# 13-AX88179A.net
KiCad netlist of a schematic drawn in Altium Designer
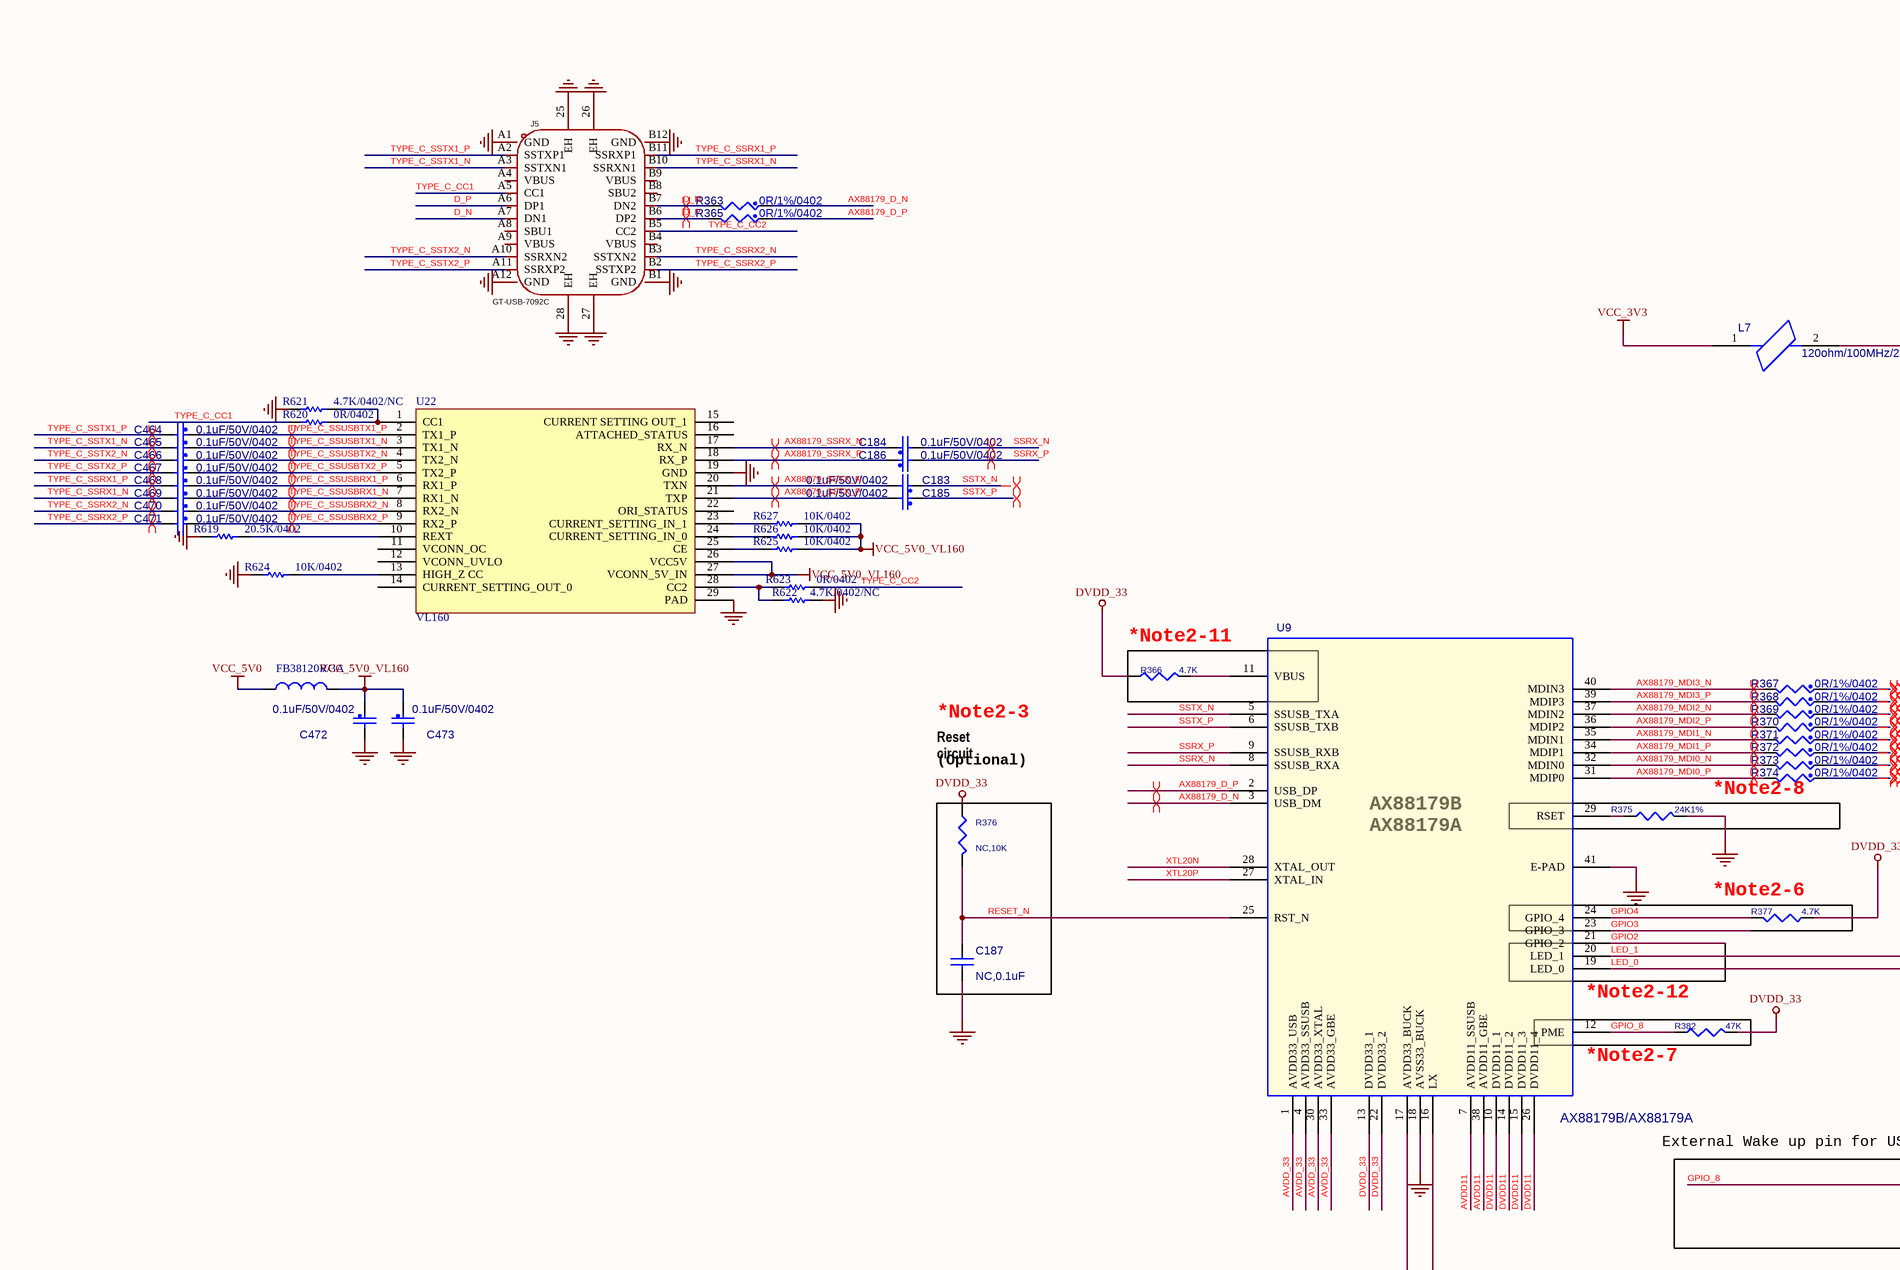
[diagram p0: 13-AX88179A.SchDoc, top left]
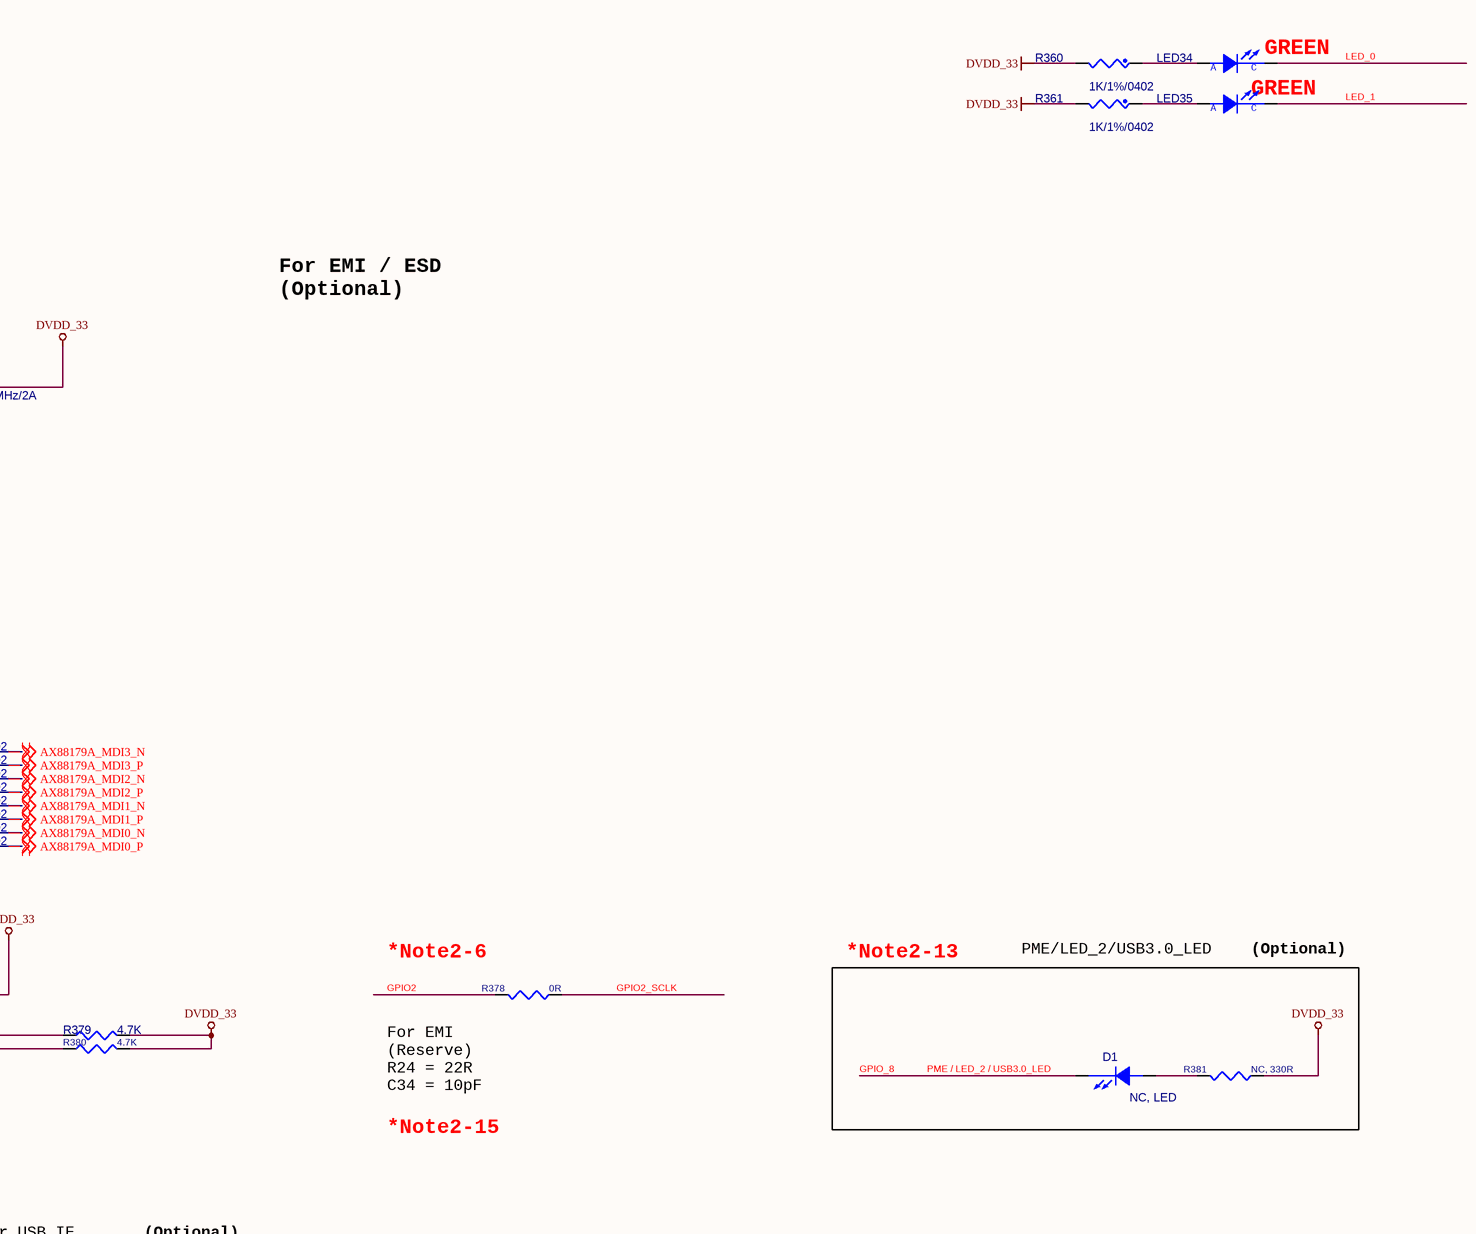
[diagram p1: 13-AX88179A.SchDoc, top right]
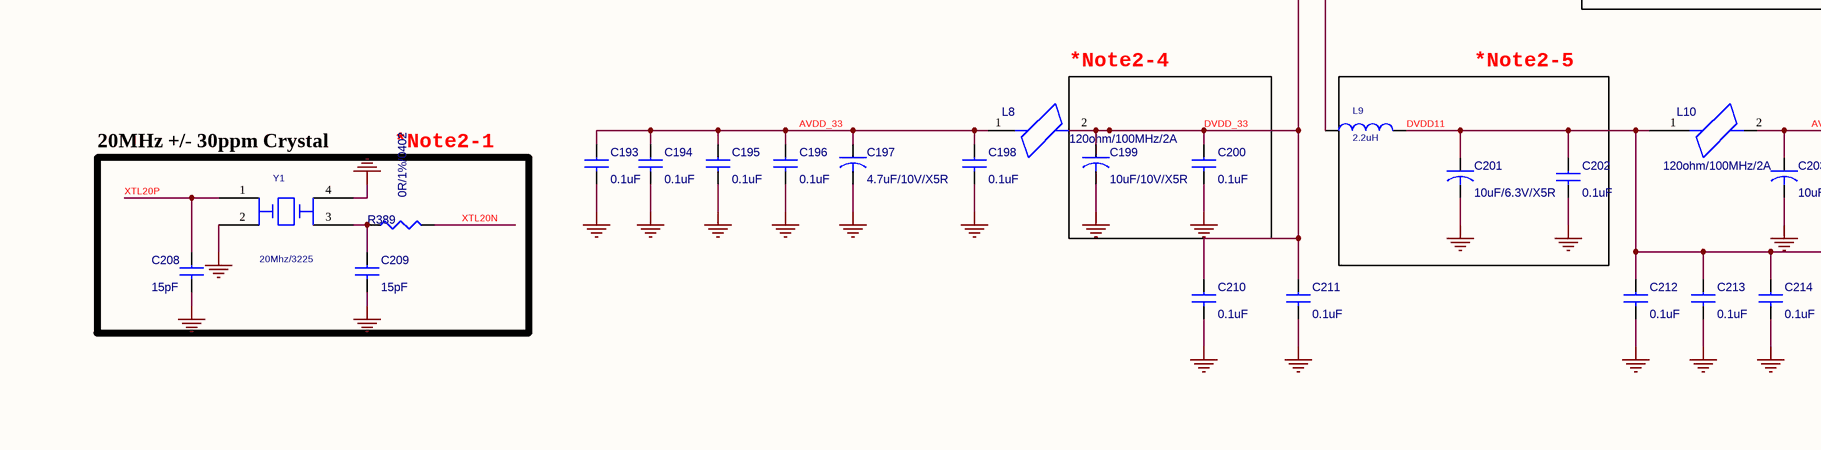
[diagram p2: 13-AX88179A.SchDoc, bottom left]
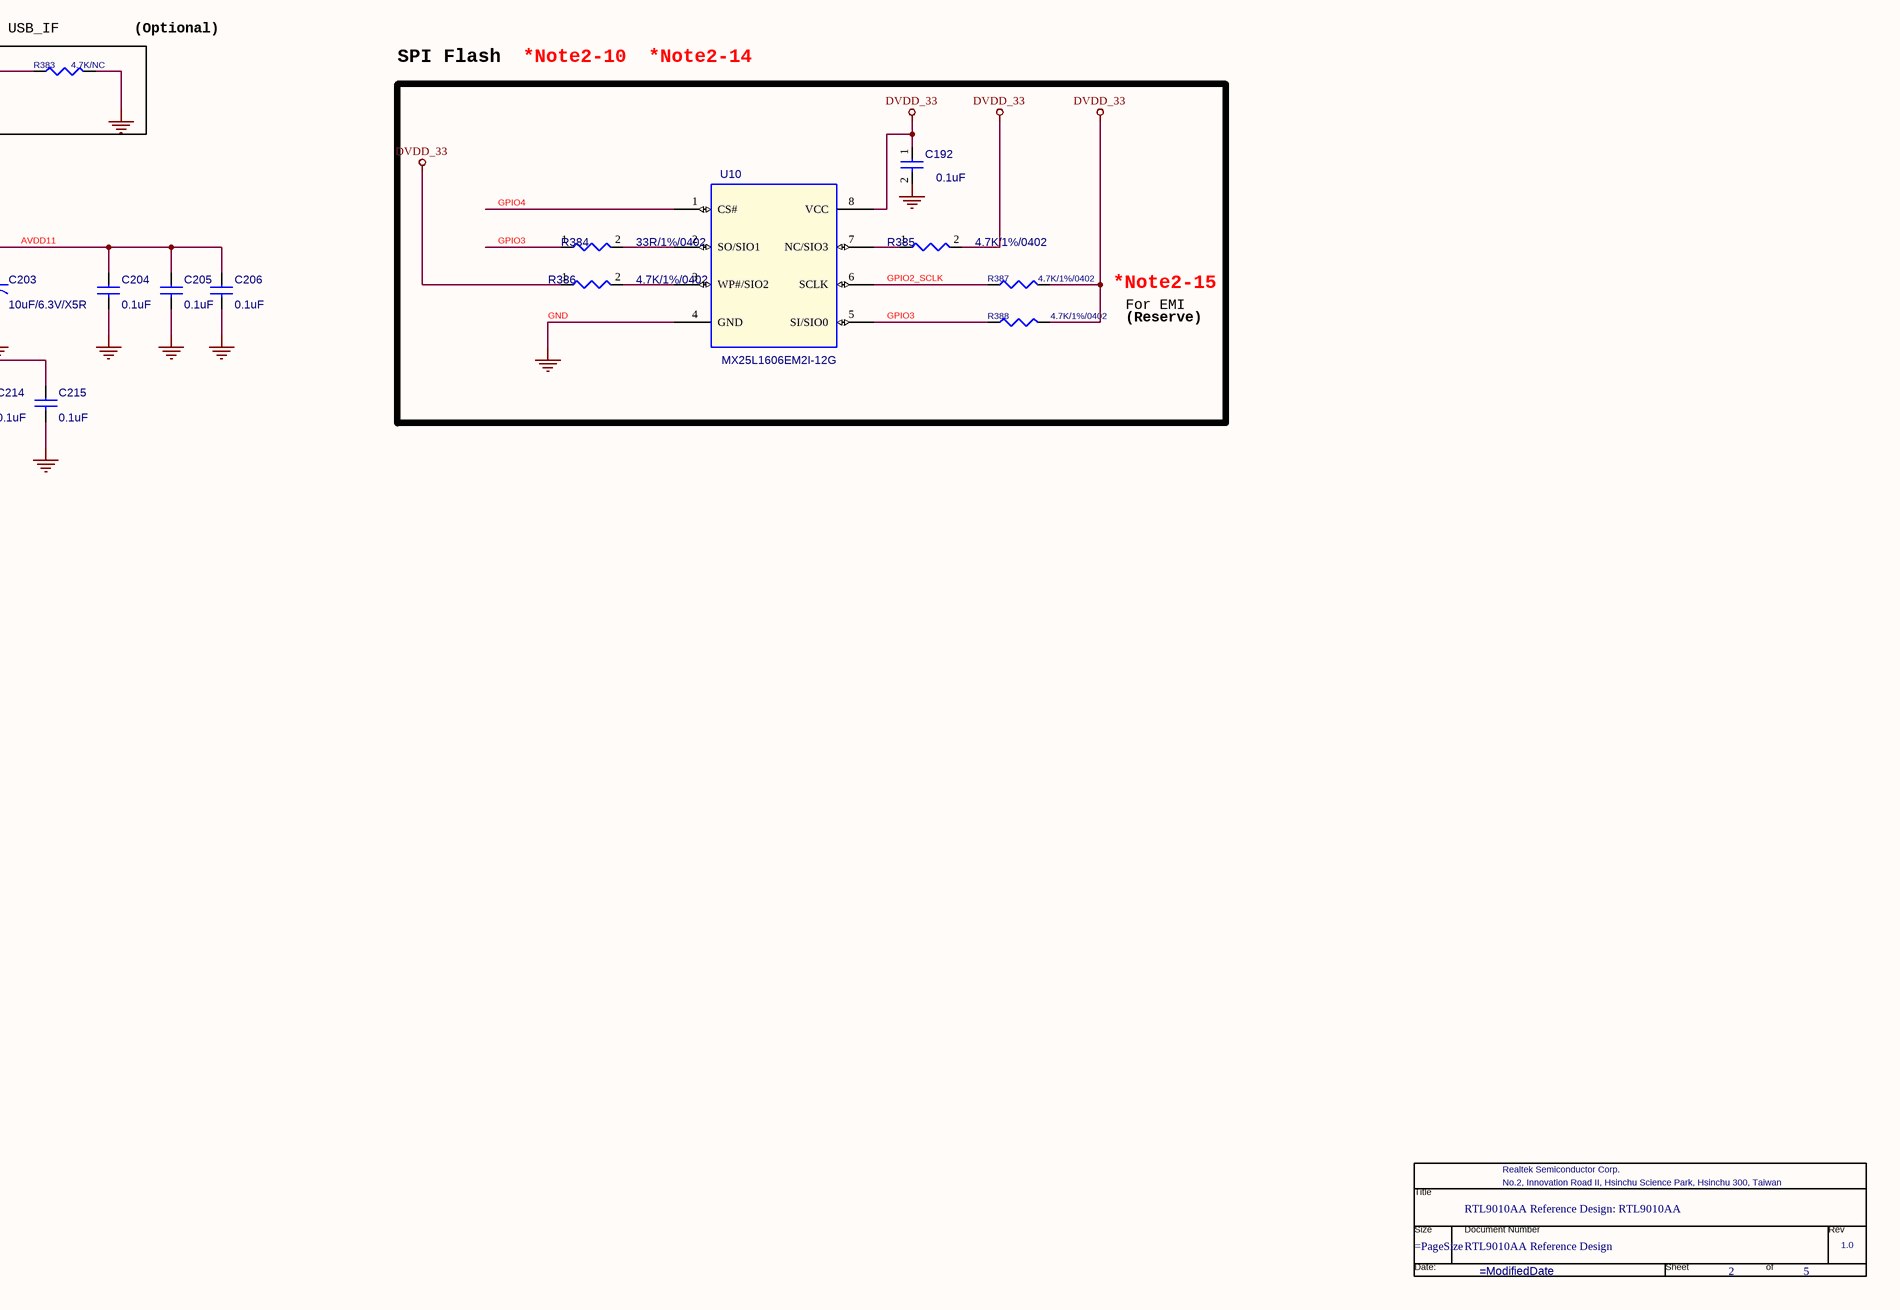
[diagram p3: 13-AX88179A.SchDoc, bottom right]

(export (version "E")
  (design (tool "Eeschema 10.0.6"))
  (components
    (comp (ref "C183")
      (value "0.1uF/50V/0402")
      (footprint "C0402")
      (description "GCM155R71H104KE02/MURATA")
      (fields (field (name "TOLERANCE") "10%") (field (name "VOLTAGE") "16V"))
      (libsource (lib "*") (part "CAP_NP"))
    )
    (comp (ref "C184")
      (value "0.1uF/50V/0402")
      (footprint "C0402")
      (description "GCM155R71H104KE02/MURATA")
      (fields (field (name "TOLERANCE") "10%") (field (name "VOLTAGE") "16V"))
      (libsource (lib "*") (part "CAP_NP"))
    )
    (comp (ref "C185")
      (value "0.1uF/50V/0402")
      (footprint "C0402")
      (description "GCM155R71H104KE02/MURATA")
      (fields (field (name "TOLERANCE") "10%") (field (name "VOLTAGE") "16V"))
      (libsource (lib "*") (part "CAP_NP"))
    )
    (comp (ref "C186")
      (value "0.1uF/50V/0402")
      (footprint "C0402")
      (description "GCM155R71H104KE02/MURATA")
      (fields (field (name "TOLERANCE") "10%") (field (name "VOLTAGE") "16V"))
      (libsource (lib "*") (part "CAP_NP"))
    )
    (comp (ref "C187")
      (value "NC,0.1uF")
      (footprint "C0402")
      (fields (field (name "Comment") "CAP NP_Dup2"))
      (libsource (lib "*") (part "CAP NP_Dup2"))
    )
    (comp (ref "C192") (value "0.1uF") (footprint "C0402") (libsource (lib "*") (part "CAP NP_0")))
    (comp (ref "C193")
      (value "0.1uF")
      (footprint "C0402")
      (fields (field (name "Comment") "CAP NP_Dup2"))
      (libsource (lib "*") (part "CAP NP_Dup2"))
    )
    (comp (ref "C194")
      (value "0.1uF")
      (footprint "C0402")
      (fields (field (name "Comment") "CAP NP_Dup2"))
      (libsource (lib "*") (part "CAP NP_Dup2"))
    )
    (comp (ref "C195")
      (value "0.1uF")
      (footprint "C0402")
      (fields (field (name "Comment") "CAP NP_Dup2"))
      (libsource (lib "*") (part "CAP NP_Dup2"))
    )
    (comp (ref "C196")
      (value "0.1uF")
      (footprint "C0402")
      (fields (field (name "Comment") "CAP NP_Dup2"))
      (libsource (lib "*") (part "CAP NP_Dup2"))
    )
    (comp (ref "C197")
      (value "4.7uF/10V/X5R")
      (footprint "C0603")
      (fields (field (name "Comment") "C_Dup1"))
      (libsource (lib "*") (part "C_Dup1"))
    )
    (comp (ref "C198")
      (value "0.1uF")
      (footprint "C0402")
      (fields (field (name "Comment") "CAP NP_Dup2"))
      (libsource (lib "*") (part "CAP NP_Dup2"))
    )
    (comp (ref "C199")
      (value "10uF/10V/X5R")
      (footprint "C0603")
      (fields (field (name "Comment") "C_Dup1"))
      (libsource (lib "*") (part "C_Dup1"))
    )
    (comp (ref "C200")
      (value "0.1uF")
      (footprint "C0402")
      (fields (field (name "Comment") "CAP NP_Dup2"))
      (libsource (lib "*") (part "CAP NP_Dup2"))
    )
    (comp (ref "C201")
      (value "10uF/6.3V/X5R")
      (footprint "C0603")
      (fields (field (name "Comment") "C_Dup1"))
      (libsource (lib "*") (part "C_Dup1"))
    )
    (comp (ref "C202")
      (value "0.1uF")
      (footprint "C0402")
      (fields (field (name "Comment") "CAP NP_Dup2"))
      (libsource (lib "*") (part "CAP NP_Dup2"))
    )
    (comp (ref "C203")
      (value "10uF/6.3V/X5R")
      (footprint "C0603")
      (fields (field (name "Comment") "C_Dup1"))
      (libsource (lib "*") (part "C_Dup1"))
    )
    (comp (ref "C204")
      (value "0.1uF")
      (footprint "C0402")
      (fields (field (name "Comment") "CAP NP_Dup2"))
      (libsource (lib "*") (part "CAP NP_Dup2"))
    )
    (comp (ref "C205")
      (value "0.1uF")
      (footprint "C0402")
      (fields (field (name "Comment") "CAP NP_Dup2"))
      (libsource (lib "*") (part "CAP NP_Dup2"))
    )
    (comp (ref "C206")
      (value "0.1uF")
      (footprint "C0402")
      (fields (field (name "Comment") "CAP NP_Dup2"))
      (libsource (lib "*") (part "CAP NP_Dup2"))
    )
    (comp (ref "C208")
      (value "15pF")
      (footprint "C0402")
      (fields (field (name "Comment") "CAP NP_Dup1"))
      (libsource (lib "*") (part "CAP NP_Dup1"))
    )
    (comp (ref "C209")
      (value "15pF")
      (footprint "C0402")
      (fields (field (name "Comment") "CAP NP_Dup1"))
      (libsource (lib "*") (part "CAP NP_Dup1"))
    )
    (comp (ref "C210")
      (value "0.1uF")
      (footprint "C0402")
      (fields (field (name "Comment") "CAP NP_Dup2"))
      (libsource (lib "*") (part "CAP NP_Dup2"))
    )
    (comp (ref "C211")
      (value "0.1uF")
      (footprint "C0402")
      (fields (field (name "Comment") "CAP NP_Dup2"))
      (libsource (lib "*") (part "CAP NP_Dup2"))
    )
    (comp (ref "C212")
      (value "0.1uF")
      (footprint "C0402")
      (fields (field (name "Comment") "CAP NP_Dup2"))
      (libsource (lib "*") (part "CAP NP_Dup2"))
    )
    (comp (ref "C213")
      (value "0.1uF")
      (footprint "C0402")
      (fields (field (name "Comment") "CAP NP_Dup2"))
      (libsource (lib "*") (part "CAP NP_Dup2"))
    )
    (comp (ref "C214")
      (value "0.1uF")
      (footprint "C0402")
      (fields (field (name "Comment") "CAP NP_Dup2"))
      (libsource (lib "*") (part "CAP NP_Dup2"))
    )
    (comp (ref "C215")
      (value "0.1uF")
      (footprint "C0402")
      (fields (field (name "Comment") "CAP NP_Dup2"))
      (libsource (lib "*") (part "CAP NP_Dup2"))
    )
    (comp (ref "C464")
      (value "0.1uF/50V/0402")
      (footprint "C0402")
      (description "GCM155R71H104KE02/MURATA")
      (fields (field (name "TOLERANCE") "10%") (field (name "VOLTAGE") "16V"))
      (libsource (lib "*") (part "CAP_NP"))
    )
    (comp (ref "C465")
      (value "0.1uF/50V/0402")
      (footprint "C0402")
      (description "GCM155R71H104KE02/MURATA")
      (fields (field (name "TOLERANCE") "10%") (field (name "VOLTAGE") "16V"))
      (libsource (lib "*") (part "CAP_NP"))
    )
    (comp (ref "C466")
      (value "0.1uF/50V/0402")
      (footprint "C0402")
      (description "GCM155R71H104KE02/MURATA")
      (fields (field (name "TOLERANCE") "10%") (field (name "VOLTAGE") "16V"))
      (libsource (lib "*") (part "CAP_NP"))
    )
    (comp (ref "C467")
      (value "0.1uF/50V/0402")
      (footprint "C0402")
      (description "GCM155R71H104KE02/MURATA")
      (fields (field (name "TOLERANCE") "10%") (field (name "VOLTAGE") "16V"))
      (libsource (lib "*") (part "CAP_NP"))
    )
    (comp (ref "C468")
      (value "0.1uF/50V/0402")
      (footprint "C0402")
      (description "GCM155R71H104KE02/MURATA")
      (fields (field (name "TOLERANCE") "10%") (field (name "VOLTAGE") "16V"))
      (libsource (lib "*") (part "CAP_NP"))
    )
    (comp (ref "C469")
      (value "0.1uF/50V/0402")
      (footprint "C0402")
      (description "GCM155R71H104KE02/MURATA")
      (fields (field (name "TOLERANCE") "10%") (field (name "VOLTAGE") "16V"))
      (libsource (lib "*") (part "CAP_NP"))
    )
    (comp (ref "C470")
      (value "0.1uF/50V/0402")
      (footprint "C0402")
      (description "GCM155R71H104KE02/MURATA")
      (fields (field (name "TOLERANCE") "10%") (field (name "VOLTAGE") "16V"))
      (libsource (lib "*") (part "CAP_NP"))
    )
    (comp (ref "C471")
      (value "0.1uF/50V/0402")
      (footprint "C0402")
      (description "GCM155R71H104KE02/MURATA")
      (fields (field (name "TOLERANCE") "10%") (field (name "VOLTAGE") "16V"))
      (libsource (lib "*") (part "CAP_NP"))
    )
    (comp (ref "C472")
      (value "0.1uF/50V/0402")
      (footprint "C0402")
      (description "GCM155R71H104KE02/MURATA")
      (fields (field (name "TOLERANCE") "10%") (field (name "VOLTAGE") "16V"))
      (libsource (lib "*") (part "CAP_NP"))
    )
    (comp (ref "C473")
      (value "0.1uF/50V/0402")
      (footprint "C0402")
      (description "GCM155R71H104KE02/MURATA")
      (fields (field (name "TOLERANCE") "10%") (field (name "VOLTAGE") "16V"))
      (libsource (lib "*") (part "CAP_NP"))
    )
    (comp (ref "D1")
      (value "NC, LED")
      (footprint "LED0603")
      (fields (field (name "Comment") "LED"))
      (libsource (lib "*") (part "LED"))
    )
    (comp (ref "FB38")
      (value "120R/3A")
      (footprint "L0603")
      (description "BLM18KG121TN1D")
      (libsource (lib "LIBS") (part "Inductor"))
    )
    (comp (ref "J5")
      (value "GT-USB-7092C")
      (footprint "USB-C-SMD_GT-USB-7092C")
      (fields (field (name "MANUFACTURER") "G-Switch(品赞)"))
      (libsource (lib "altium-import") (part "root_0_GT-USB-7092C_"))
    )
    (comp (ref "L7")
      (value "120ohm/100MHz/2A")
      (footprint "L0603")
      (description "BLM18EG121SH1D/MURATA")
      (fields (field (name "Comment") "BEAD_FERRITE"))
      (libsource (lib "*") (part "BEAD_FERRITE"))
    )
    (comp (ref "L8")
      (value "120ohm/100MHz/2A")
      (footprint "L0603")
      (description "BLM18EG121SH1D/MURATA")
      (fields (field (name "Comment") "BEAD_FERRITE"))
      (libsource (lib "*") (part "BEAD_FERRITE"))
    )
    (comp (ref "L9")
      (value "2.2uH")
      (footprint "L0805")
      (fields (field (name "Comment") "INDUCTOR"))
      (libsource (lib "*") (part "INDUCTOR"))
    )
    (comp (ref "L10")
      (value "120ohm/100MHz/2A")
      (footprint "L0603")
      (description "BLM18EG121SH1D/MURATA")
      (fields (field (name "Comment") "BEAD_FERRITE"))
      (libsource (lib "*") (part "BEAD_FERRITE"))
    )
    (comp (ref "LED34")
      (value "LED_P2_Dup1")
      (footprint "LED0603")
      (description "NCD0603G1/NATIONSTAR")
      (libsource (lib "*") (part "LED_P2_Dup1"))
    )
    (comp (ref "LED35")
      (value "LED_P2_Dup1")
      (footprint "LED0603")
      (description "NCD0603B1/NATIONSTAR")
      (libsource (lib "*") (part "LED_P2_Dup1"))
    )
    (comp (ref "R360")
      (value "1K/1%/0402")
      (footprint "R0402")
      (description "AC0402FR-071KL/YAGEO")
      (fields (field (name "Comment") "RES_Dup2"))
      (libsource (lib "*") (part "RES_Dup2"))
    )
    (comp (ref "R361")
      (value "1K/1%/0402")
      (footprint "R0402")
      (description "AC0402FR-071KL/YAGEO")
      (fields (field (name "Comment") "RES_Dup2"))
      (libsource (lib "*") (part "RES_Dup2"))
    )
    (comp (ref "R363")
      (value "0R/1%/0402")
      (footprint "R0402")
      (description "AC0402FR-070RL/YAGEO")
      (fields (field (name "TOLERANCE") "1%") (field (name "Comment") "RES_Dup2"))
      (libsource (lib "*") (part "RES_Dup2"))
    )
    (comp (ref "R365")
      (value "0R/1%/0402")
      (footprint "R0402")
      (description "AC0402FR-070RL/YAGEO")
      (fields (field (name "TOLERANCE") "1%") (field (name "Comment") "RES_Dup2"))
      (libsource (lib "*") (part "RES_Dup2"))
    )
    (comp (ref "R366") (value "4.7K") (footprint "R0402") (libsource (lib "*") (part "R_Dup1")))
    (comp (ref "R367")
      (value "0R/1%/0402")
      (footprint "R0402")
      (description "AC0402FR-070RL/YAGEO")
      (fields (field (name "TOLERANCE") "1%") (field (name "Comment") "RES_Dup2"))
      (libsource (lib "*") (part "RES_Dup2"))
    )
    (comp (ref "R368")
      (value "0R/1%/0402")
      (footprint "R0402")
      (description "AC0402FR-070RL/YAGEO")
      (fields (field (name "TOLERANCE") "1%") (field (name "Comment") "RES_Dup2"))
      (libsource (lib "*") (part "RES_Dup2"))
    )
    (comp (ref "R369")
      (value "0R/1%/0402")
      (footprint "R0402")
      (description "AC0402FR-070RL/YAGEO")
      (fields (field (name "TOLERANCE") "1%") (field (name "Comment") "RES_Dup2"))
      (libsource (lib "*") (part "RES_Dup2"))
    )
    (comp (ref "R370")
      (value "0R/1%/0402")
      (footprint "R0402")
      (description "AC0402FR-070RL/YAGEO")
      (fields (field (name "TOLERANCE") "1%") (field (name "Comment") "RES_Dup2"))
      (libsource (lib "*") (part "RES_Dup2"))
    )
    (comp (ref "R371")
      (value "0R/1%/0402")
      (footprint "R0402")
      (description "AC0402FR-070RL/YAGEO")
      (fields (field (name "TOLERANCE") "1%") (field (name "Comment") "RES_Dup2"))
      (libsource (lib "*") (part "RES_Dup2"))
    )
    (comp (ref "R372")
      (value "0R/1%/0402")
      (footprint "R0402")
      (description "AC0402FR-070RL/YAGEO")
      (fields (field (name "TOLERANCE") "1%") (field (name "Comment") "RES_Dup2"))
      (libsource (lib "*") (part "RES_Dup2"))
    )
    (comp (ref "R373")
      (value "0R/1%/0402")
      (footprint "R0402")
      (description "AC0402FR-070RL/YAGEO")
      (fields (field (name "TOLERANCE") "1%") (field (name "Comment") "RES_Dup2"))
      (libsource (lib "*") (part "RES_Dup2"))
    )
    (comp (ref "R374")
      (value "0R/1%/0402")
      (footprint "R0402")
      (description "AC0402FR-070RL/YAGEO")
      (fields (field (name "TOLERANCE") "1%") (field (name "Comment") "RES_Dup2"))
      (libsource (lib "*") (part "RES_Dup2"))
    )
    (comp (ref "R375")
      (value "24K1%")
      (footprint "R0402")
      (fields (field (name "Comment") "24K/1%/0402"))
      (libsource (lib "*") (part "R"))
    )
    (comp (ref "R376")
      (value "NC,10K")
      (footprint "R0402")
      (fields (field (name "Comment") "R"))
      (libsource (lib "*") (part "R"))
    )
    (comp (ref "R377")
      (value "4.7K")
      (footprint "R0402")
      (fields (field (name "Comment") "R_Dup1"))
      (libsource (lib "*") (part "R_Dup1"))
    )
    (comp (ref "R378")
      (value "0R")
      (footprint "R0402")
      (fields (field (name "Comment") "R_Dup2"))
      (libsource (lib "*") (part "R_Dup2"))
    )
    (comp (ref "R379")
      (value "4.7K")
      (footprint "R0402")
      (fields (field (name "Comment") "R_Dup4"))
      (libsource (lib "*") (part "R_Dup4"))
    )
    (comp (ref "R380")
      (value "4.7K")
      (footprint "R0402")
      (fields (field (name "Comment") "R_Dup1"))
      (libsource (lib "*") (part "R_Dup1"))
    )
    (comp (ref "R381")
      (value "NC, 330R")
      (footprint "R0402")
      (fields (field (name "Comment") "R_Dup2"))
      (libsource (lib "*") (part "R_Dup2"))
    )
    (comp (ref "R382")
      (value "47K")
      (footprint "R0402")
      (fields (field (name "Comment") "R_Dup2"))
      (libsource (lib "*") (part "R_Dup2"))
    )
    (comp (ref "R383")
      (value "4.7K/NC")
      (footprint "R0402")
      (fields (field (name "Comment") "R_Dup2"))
      (libsource (lib "*") (part "R_Dup2"))
    )
    (comp (ref "R384") (value "33R/1%/0402") (footprint "R0402") (libsource (lib "*") (part "R_2")))
    (comp (ref "R385") (value "4.7K/1%/0402") (footprint "R0402") (libsource (lib "*") (part "R_1")))
    (comp (ref "R386") (value "4.7K/1%/0402") (footprint "R0402") (libsource (lib "*") (part "R_0")))
    (comp (ref "R387") (value "4.7K/1%/0402") (footprint "R0402") (libsource (lib "*") (part "R_3")))
    (comp (ref "R388") (value "4.7K/1%/0402") (footprint "R0402") (libsource (lib "*") (part "R_Dup2")))
    (comp (ref "R389") (value "0R/1%/0402") (footprint "R0402") (libsource (lib "*") (part "R_Dup4")))
    (comp (ref "R619")
      (value "20.5K/0402")
      (footprint "R0402")
      (description "Semiconductor Resistor")
      (libsource (lib "LIBS") (part "Res Semi"))
    )
    (comp (ref "R620")
      (value "0R/0402")
      (footprint "R0402")
      (description "Semiconductor Resistor")
      (libsource (lib "LIBS") (part "Res Semi"))
    )
    (comp (ref "R621")
      (value "4.7K/0402/NC")
      (footprint "R0402")
      (description "Semiconductor Resistor")
      (libsource (lib "LIBS") (part "Res Semi"))
    )
    (comp (ref "R622")
      (value "4.7K/0402/NC")
      (footprint "R0402")
      (description "Semiconductor Resistor")
      (libsource (lib "LIBS") (part "Res Semi"))
    )
    (comp (ref "R623")
      (value "0R/0402")
      (footprint "R0402")
      (description "Semiconductor Resistor")
      (libsource (lib "LIBS") (part "Res Semi"))
    )
    (comp (ref "R624")
      (value "10K/0402")
      (footprint "R0402")
      (description "Semiconductor Resistor")
      (libsource (lib "LIBS") (part "Res Semi"))
    )
    (comp (ref "R625")
      (value "10K/0402")
      (footprint "R0402")
      (description "Semiconductor Resistor")
      (libsource (lib "LIBS") (part "Res Semi"))
    )
    (comp (ref "R626")
      (value "10K/0402")
      (footprint "R0402")
      (description "Semiconductor Resistor")
      (libsource (lib "LIBS") (part "Res Semi"))
    )
    (comp (ref "R627")
      (value "10K/0402")
      (footprint "R0402")
      (description "Semiconductor Resistor")
      (libsource (lib "LIBS") (part "Res Semi"))
    )
    (comp (ref "U9")
      (value "AX88179B/AX88179A")
      (footprint "AX88179")
      (libsource (lib "*") (part "USB3 TO Gbe_1"))
    )
    (comp (ref "U10")
      (value "MX25L1606EM2I-12G")
      (footprint "MX25L1606EM2I-12G")
      (libsource (lib "*") (part "MX25L1606E_2"))
    )
    (comp (ref "U22") (value "VL160") (footprint "VL160") (libsource (lib "LIBS") (part "vl60")))
    (comp (ref "Y1") (value "20Mhz/3225") (footprint "3225") (libsource (lib "*") (part "CRYSTAL4/SM_0")))
  )
  (nets
    (net (code "1") (name "/AVDD11") (class "Default")
      (node (ref "C203") (pin "1") (pinfunction "1_1") (pintype "passive"))
      (node (ref "C204") (pin "1") (pinfunction "1_1") (pintype "passive"))
      (node (ref "C205") (pin "1") (pinfunction "1_1") (pintype "passive"))
      (node (ref "C206") (pin "1") (pinfunction "1_1") (pintype "passive"))
      (node (ref "L10") (pin "2") (pinfunction "2_2") (pintype "passive"))
      (node (ref "U9") (pin "38") (pinfunction "AVDD11_GBE_38") (pintype "passive"))
      (node (ref "U9") (pin "7") (pinfunction "AVDD11_SSUSB_7") (pintype "passive"))
    )
    (net (code "2") (name "/AVDD_33") (class "Default")
      (node (ref "C193") (pin "1") (pinfunction "1_1") (pintype "passive"))
      (node (ref "C194") (pin "1") (pinfunction "1_1") (pintype "passive"))
      (node (ref "C195") (pin "1") (pinfunction "1_1") (pintype "passive"))
      (node (ref "C196") (pin "1") (pinfunction "1_1") (pintype "passive"))
      (node (ref "C197") (pin "1") (pinfunction "1_1") (pintype "passive"))
      (node (ref "C198") (pin "1") (pinfunction "1_1") (pintype "passive"))
      (node (ref "L8") (pin "1") (pinfunction "1_1") (pintype "passive"))
      (node (ref "U9") (pin "1") (pinfunction "AVDD33_USB_1") (pintype "passive"))
      (node (ref "U9") (pin "30") (pinfunction "AVDD33_XTAL_30") (pintype "passive"))
      (node (ref "U9") (pin "33") (pinfunction "AVDD33_GBE_33") (pintype "passive"))
      (node (ref "U9") (pin "4") (pinfunction "AVDD33_SSUSB_4") (pintype "passive"))
    )
    (net (code "3") (name "/AX88179_D_N") (class "Default")
      (node (ref "R363") (pin "1") (pinfunction "1_1") (pintype "passive"))
      (node (ref "U9") (pin "3") (pinfunction "USB_DM_3") (pintype "passive"))
    )
    (net (code "4") (name "/AX88179_D_P") (class "Default")
      (node (ref "R365") (pin "1") (pinfunction "1_1") (pintype "passive"))
      (node (ref "U9") (pin "2") (pinfunction "USB_DP_2") (pintype "passive"))
    )
    (net (code "5") (name "/AX88179_MDI0_N") (class "Default")
      (node (ref "R373") (pin "2") (pinfunction "2_2") (pintype "passive"))
      (node (ref "U9") (pin "32") (pinfunction "MDIN0_32") (pintype "passive"))
    )
    (net (code "6") (name "/AX88179_MDI0_P") (class "Default")
      (node (ref "R374") (pin "2") (pinfunction "2_2") (pintype "passive"))
      (node (ref "U9") (pin "31") (pinfunction "MDIP0_31") (pintype "passive"))
    )
    (net (code "7") (name "/AX88179_MDI1_N") (class "Default")
      (node (ref "R371") (pin "2") (pinfunction "2_2") (pintype "passive"))
      (node (ref "U9") (pin "35") (pinfunction "MDIN1_35") (pintype "passive"))
    )
    (net (code "8") (name "/AX88179_MDI1_P") (class "Default")
      (node (ref "R372") (pin "2") (pinfunction "2_2") (pintype "passive"))
      (node (ref "U9") (pin "34") (pinfunction "MDIP1_34") (pintype "passive"))
    )
    (net (code "9") (name "/AX88179_MDI2_N") (class "Default")
      (node (ref "R369") (pin "2") (pinfunction "2_2") (pintype "passive"))
      (node (ref "U9") (pin "37") (pinfunction "MDIN2_37") (pintype "passive"))
    )
    (net (code "10") (name "/AX88179_MDI2_P") (class "Default")
      (node (ref "R370") (pin "2") (pinfunction "2_2") (pintype "passive"))
      (node (ref "U9") (pin "36") (pinfunction "MDIP2_36") (pintype "passive"))
    )
    (net (code "11") (name "/AX88179_MDI3_N") (class "Default")
      (node (ref "R367") (pin "2") (pinfunction "2_2") (pintype "passive"))
      (node (ref "U9") (pin "40") (pinfunction "MDIN3_40") (pintype "passive"))
    )
    (net (code "12") (name "/AX88179_MDI3_P") (class "Default")
      (node (ref "R368") (pin "2") (pinfunction "2_2") (pintype "passive"))
      (node (ref "U9") (pin "39") (pinfunction "MDIP3_39") (pintype "passive"))
    )
    (net (code "13") (name "/AX88179_SSRX_N") (class "Default")
      (node (ref "C184") (pin "1") (pinfunction "1_1") (pintype "passive"))
      (node (ref "U22") (pin "17") (pinfunction "RX_N_17") (pintype "passive"))
    )
    (net (code "14") (name "/AX88179_SSRX_P") (class "Default")
      (node (ref "C186") (pin "1") (pinfunction "1_1") (pintype "passive"))
      (node (ref "U22") (pin "18") (pinfunction "RX_P_18") (pintype "passive"))
    )
    (net (code "15") (name "/AX88179_SSTX_N") (class "Default")
      (node (ref "C183") (pin "2") (pinfunction "2_2") (pintype "passive"))
      (node (ref "U22") (pin "20") (pinfunction "TXN_20") (pintype "passive"))
    )
    (net (code "16") (name "/AX88179_SSTX_P") (class "Default")
      (node (ref "C185") (pin "2") (pinfunction "2_2") (pintype "passive"))
      (node (ref "U22") (pin "21") (pinfunction "TXP_21") (pintype "passive"))
    )
    (net (code "17") (name "/DVDD11") (class "Default")
      (node (ref "C201") (pin "1") (pinfunction "1_1") (pintype "passive"))
      (node (ref "C202") (pin "1") (pinfunction "1_1") (pintype "passive"))
      (node (ref "C212") (pin "1") (pinfunction "1_1") (pintype "passive"))
      (node (ref "C213") (pin "1") (pinfunction "1_1") (pintype "passive"))
      (node (ref "C214") (pin "1") (pinfunction "1_1") (pintype "passive"))
      (node (ref "C215") (pin "1") (pinfunction "1_1") (pintype "passive"))
      (node (ref "L10") (pin "1") (pinfunction "1_1") (pintype "passive"))
      (node (ref "L9") (pin "2") (pinfunction "2_2") (pintype "passive"))
      (node (ref "U9") (pin "10") (pinfunction "DVDD11_1_10") (pintype "passive"))
      (node (ref "U9") (pin "14") (pinfunction "DVDD11_2_14") (pintype "passive"))
      (node (ref "U9") (pin "15") (pinfunction "DVDD11_3_15") (pintype "passive"))
      (node (ref "U9") (pin "26") (pinfunction "DVDD11_4_26") (pintype "passive"))
    )
    (net (code "18") (name "/D_N") (class "Default")
      (node (ref "J5") (pin "A7") (pinfunction "DN1_A7") (pintype "passive"))
      (node (ref "J5") (pin "B7") (pinfunction "DN2_B7") (pintype "passive"))
      (node (ref "R363") (pin "2") (pinfunction "2_2") (pintype "passive"))
    )
    (net (code "19") (name "/D_P") (class "Default")
      (node (ref "J5") (pin "A6") (pinfunction "DP1_A6") (pintype "passive"))
      (node (ref "J5") (pin "B6") (pinfunction "DP2_B6") (pintype "passive"))
      (node (ref "R365") (pin "2") (pinfunction "2_2") (pintype "passive"))
    )
    (net (code "20") (name "/GPIO2") (class "Default")
      (node (ref "R378") (pin "2") (pinfunction "2_2") (pintype "passive"))
      (node (ref "U9") (pin "21") (pinfunction "GPIO_2_21") (pintype "passive"))
    )
    (net (code "21") (name "/GPIO2_SCLK") (class "Default")
      (node (ref "R378") (pin "1") (pinfunction "1_1") (pintype "passive"))
      (node (ref "R387") (pin "1") (pinfunction "1_1") (pintype "passive"))
      (node (ref "U10") (pin "6") (pinfunction "SCLK_6") (pintype "bidirectional"))
    )
    (net (code "22") (name "/GPIO3") (class "Default")
      (node (ref "R384") (pin "1") (pinfunction "1_1") (pintype "passive"))
      (node (ref "R388") (pin "1") (pinfunction "1_1") (pintype "passive"))
      (node (ref "U10") (pin "5") (pinfunction "SI/SIO0_5") (pintype "bidirectional"))
      (node (ref "U9") (pin "23") (pinfunction "GPIO_3_23") (pintype "passive"))
    )
    (net (code "23") (name "/GPIO4") (class "Default")
      (node (ref "R377") (pin "2") (pinfunction "2_2") (pintype "passive"))
      (node (ref "U10") (pin "1") (pinfunction "CS#_1") (pintype "bidirectional"))
      (node (ref "U9") (pin "24") (pinfunction "GPIO_4_24") (pintype "passive"))
    )
    (net (code "24") (name "/GPIO_8") (class "Default")
      (node (ref "D1") (pin "2") (pinfunction "CATHODE_2") (pintype "passive"))
      (node (ref "R382") (pin "1") (pinfunction "1_1") (pintype "passive"))
      (node (ref "R383") (pin "1") (pinfunction "1_1") (pintype "passive"))
      (node (ref "U9") (pin "12") (pinfunction "PME_12") (pintype "passive"))
    )
    (net (code "25") (name "/LED_0") (class "Default")
      (node (ref "LED34") (pin "2") (pinfunction "CATHODE_2") (pintype "passive"))
      (node (ref "R380") (pin "1") (pinfunction "1_1") (pintype "passive"))
      (node (ref "U9") (pin "19") (pinfunction "LED_0_19") (pintype "passive"))
    )
    (net (code "26") (name "/LED_1") (class "Default")
      (node (ref "LED35") (pin "2") (pinfunction "CATHODE_2") (pintype "passive"))
      (node (ref "R379") (pin "1") (pinfunction "1_1") (pintype "passive"))
      (node (ref "U9") (pin "20") (pinfunction "LED_1_20") (pintype "passive"))
    )
    (net (code "27") (name "/RESET_N") (class "Default")
      (node (ref "C187") (pin "1") (pinfunction "1_1") (pintype "passive"))
      (node (ref "R376") (pin "2") (pinfunction "2_2") (pintype "passive"))
      (node (ref "U9") (pin "25") (pinfunction "RST_N_25") (pintype "passive"))
    )
    (net (code "28") (name "/SSRX_N") (class "Default")
      (node (ref "C184") (pin "2") (pinfunction "2_2") (pintype "passive"))
      (node (ref "U9") (pin "8") (pinfunction "SSUSB_RXA_8") (pintype "passive"))
    )
    (net (code "29") (name "/SSRX_P") (class "Default")
      (node (ref "C186") (pin "2") (pinfunction "2_2") (pintype "passive"))
      (node (ref "U9") (pin "9") (pinfunction "SSUSB_RXB_9") (pintype "passive"))
    )
    (net (code "30") (name "/SSTX_N") (class "Default")
      (node (ref "C183") (pin "1") (pinfunction "1_1") (pintype "passive"))
      (node (ref "U9") (pin "5") (pinfunction "SSUSB_TXA_5") (pintype "passive"))
    )
    (net (code "31") (name "/SSTX_P") (class "Default")
      (node (ref "C185") (pin "1") (pinfunction "1_1") (pintype "passive"))
      (node (ref "U9") (pin "6") (pinfunction "SSUSB_TXB_6") (pintype "passive"))
    )
    (net (code "32") (name "/TYPE_C_CC1") (class "Default")
      (node (ref "J5") (pin "A5") (pinfunction "CC1_A5") (pintype "passive"))
      (node (ref "R620") (pin "1") (pinfunction "1_1") (pintype "passive"))
    )
    (net (code "33") (name "/TYPE_C_CC2") (class "Default")
      (node (ref "J5") (pin "B5") (pinfunction "CC2_B5") (pintype "passive"))
      (node (ref "R623") (pin "2") (pinfunction "2_2") (pintype "passive"))
    )
    (net (code "34") (name "/TYPE_C_SSRX1_N") (class "Default")
      (node (ref "C469") (pin "2") (pinfunction "2_2") (pintype "passive"))
      (node (ref "J5") (pin "B10") (pinfunction "SSRXN1_B10") (pintype "passive"))
    )
    (net (code "35") (name "/TYPE_C_SSRX1_P") (class "Default")
      (node (ref "C468") (pin "2") (pinfunction "2_2") (pintype "passive"))
      (node (ref "J5") (pin "B11") (pinfunction "SSRXP1_B11") (pintype "passive"))
    )
    (net (code "36") (name "/TYPE_C_SSRX2_N") (class "Default")
      (node (ref "C470") (pin "2") (pinfunction "2_2") (pintype "passive"))
      (node (ref "J5") (pin "B3") (pinfunction "SSTXN2_B3") (pintype "passive"))
    )
    (net (code "37") (name "/TYPE_C_SSRX2_P") (class "Default")
      (node (ref "C471") (pin "2") (pinfunction "2_2") (pintype "passive"))
      (node (ref "J5") (pin "B2") (pinfunction "SSTXP2_B2") (pintype "passive"))
    )
    (net (code "38") (name "/TYPE_C_SSTX1_N") (class "Default")
      (node (ref "C465") (pin "2") (pinfunction "2_2") (pintype "passive"))
      (node (ref "J5") (pin "A3") (pinfunction "SSTXN1_A3") (pintype "passive"))
    )
    (net (code "39") (name "/TYPE_C_SSTX1_P") (class "Default")
      (node (ref "C464") (pin "2") (pinfunction "2_2") (pintype "passive"))
      (node (ref "J5") (pin "A2") (pinfunction "SSTXP1_A2") (pintype "passive"))
    )
    (net (code "40") (name "/TYPE_C_SSTX2_N") (class "Default")
      (node (ref "C466") (pin "2") (pinfunction "2_2") (pintype "passive"))
      (node (ref "J5") (pin "A10") (pinfunction "SSRXN2_A10") (pintype "passive"))
    )
    (net (code "41") (name "/TYPE_C_SSTX2_P") (class "Default")
      (node (ref "C467") (pin "2") (pinfunction "2_2") (pintype "passive"))
      (node (ref "J5") (pin "A11") (pinfunction "SSRXP2_A11") (pintype "passive"))
    )
    (net (code "42") (name "/TYPE_C_SSUSBRX1_N") (class "Default")
      (node (ref "C469") (pin "1") (pinfunction "1_1") (pintype "passive"))
      (node (ref "U22") (pin "7") (pinfunction "RX1_N_7") (pintype "passive"))
    )
    (net (code "43") (name "/TYPE_C_SSUSBRX1_P") (class "Default")
      (node (ref "C468") (pin "1") (pinfunction "1_1") (pintype "passive"))
      (node (ref "U22") (pin "6") (pinfunction "RX1_P_6") (pintype "passive"))
    )
    (net (code "44") (name "/TYPE_C_SSUSBRX2_N") (class "Default")
      (node (ref "C470") (pin "1") (pinfunction "1_1") (pintype "passive"))
      (node (ref "U22") (pin "8") (pinfunction "RX2_N_8") (pintype "passive"))
    )
    (net (code "45") (name "/TYPE_C_SSUSBRX2_P") (class "Default")
      (node (ref "C471") (pin "1") (pinfunction "1_1") (pintype "passive"))
      (node (ref "U22") (pin "9") (pinfunction "RX2_P_9") (pintype "passive"))
    )
    (net (code "46") (name "/TYPE_C_SSUSBTX1_N") (class "Default")
      (node (ref "C465") (pin "1") (pinfunction "1_1") (pintype "passive"))
      (node (ref "U22") (pin "3") (pinfunction "TX1_N_3") (pintype "passive"))
    )
    (net (code "47") (name "/TYPE_C_SSUSBTX1_P") (class "Default")
      (node (ref "C464") (pin "1") (pinfunction "1_1") (pintype "passive"))
      (node (ref "U22") (pin "2") (pinfunction "TX1_P_2") (pintype "passive"))
    )
    (net (code "48") (name "/TYPE_C_SSUSBTX2_N") (class "Default")
      (node (ref "C466") (pin "1") (pinfunction "1_1") (pintype "passive"))
      (node (ref "U22") (pin "4") (pinfunction "TX2_N_4") (pintype "passive"))
    )
    (net (code "49") (name "/TYPE_C_SSUSBTX2_P") (class "Default")
      (node (ref "C467") (pin "1") (pinfunction "1_1") (pintype "passive"))
      (node (ref "U22") (pin "5") (pinfunction "TX2_P_5") (pintype "passive"))
    )
    (net (code "50") (name "/XTL20N") (class "Default")
      (node (ref "R389") (pin "2") (pinfunction "2_2") (pintype "passive"))
      (node (ref "U9") (pin "28") (pinfunction "XTAL_OUT_28") (pintype "passive"))
    )
    (net (code "51") (name "/XTL20P") (class "Default")
      (node (ref "C208") (pin "1") (pinfunction "1_1") (pintype "passive"))
      (node (ref "U9") (pin "27") (pinfunction "XTAL_IN_27") (pintype "passive"))
      (node (ref "Y1") (pin "1") (pinfunction "1_1") (pintype "passive"))
    )
    (net (code "52") (name "AX88179A_MDI0_N") (class "Default")
      (node (ref "R373") (pin "1") (pinfunction "1_1") (pintype "passive"))
    )
    (net (code "53") (name "AX88179A_MDI0_P") (class "Default")
      (node (ref "R374") (pin "1") (pinfunction "1_1") (pintype "passive"))
    )
    (net (code "54") (name "AX88179A_MDI1_N") (class "Default")
      (node (ref "R371") (pin "1") (pinfunction "1_1") (pintype "passive"))
    )
    (net (code "55") (name "AX88179A_MDI1_P") (class "Default")
      (node (ref "R372") (pin "1") (pinfunction "1_1") (pintype "passive"))
    )
    (net (code "56") (name "AX88179A_MDI2_N") (class "Default")
      (node (ref "R369") (pin "1") (pinfunction "1_1") (pintype "passive"))
    )
    (net (code "57") (name "AX88179A_MDI2_P") (class "Default")
      (node (ref "R370") (pin "1") (pinfunction "1_1") (pintype "passive"))
    )
    (net (code "58") (name "AX88179A_MDI3_N") (class "Default")
      (node (ref "R367") (pin "1") (pinfunction "1_1") (pintype "passive"))
    )
    (net (code "59") (name "AX88179A_MDI3_P") (class "Default")
      (node (ref "R368") (pin "1") (pinfunction "1_1") (pintype "passive"))
    )
    (net (code "60") (name "DVDD_33") (class "Default")
      (node (ref "C192") (pin "1") (pinfunction "1_1") (pintype "passive"))
      (node (ref "C199") (pin "1") (pinfunction "1_1") (pintype "passive"))
      (node (ref "C200") (pin "1") (pinfunction "1_1") (pintype "passive"))
      (node (ref "C210") (pin "1") (pinfunction "1_1") (pintype "passive"))
      (node (ref "C211") (pin "1") (pinfunction "1_1") (pintype "passive"))
      (node (ref "L7") (pin "2") (pinfunction "2_2") (pintype "passive"))
      (node (ref "L8") (pin "2") (pinfunction "2_2") (pintype "passive"))
      (node (ref "R360") (pin "2") (pinfunction "2_2") (pintype "passive"))
      (node (ref "R361") (pin "2") (pinfunction "2_2") (pintype "passive"))
      (node (ref "R366") (pin "1") (pinfunction "1_1") (pintype "passive"))
      (node (ref "R376") (pin "1") (pinfunction "1_1") (pintype "passive"))
      (node (ref "R377") (pin "1") (pinfunction "1_1") (pintype "passive"))
      (node (ref "R379") (pin "2") (pinfunction "2_2") (pintype "passive"))
      (node (ref "R380") (pin "2") (pinfunction "2_2") (pintype "passive"))
      (node (ref "R381") (pin "1") (pinfunction "1_1") (pintype "passive"))
      (node (ref "R382") (pin "2") (pinfunction "2_2") (pintype "passive"))
      (node (ref "R385") (pin "2") (pinfunction "2_2") (pintype "passive"))
      (node (ref "R386") (pin "1") (pinfunction "1_1") (pintype "passive"))
      (node (ref "R387") (pin "2") (pinfunction "2_2") (pintype "passive"))
      (node (ref "R388") (pin "2") (pinfunction "2_2") (pintype "passive"))
      (node (ref "U10") (pin "8") (pinfunction "VCC_8") (pintype "power_in"))
      (node (ref "U9") (pin "13") (pinfunction "DVDD33_1_13") (pintype "passive"))
      (node (ref "U9") (pin "17") (pinfunction "AVDD33_BUCK_17") (pintype "passive"))
      (node (ref "U9") (pin "22") (pinfunction "DVDD33_2_22") (pintype "passive"))
    )
    (net (code "61") (name "GND") (class "Default")
      (node (ref "C187") (pin "2") (pinfunction "2_2") (pintype "passive"))
      (node (ref "C192") (pin "2") (pinfunction "2_2") (pintype "passive"))
      (node (ref "C193") (pin "2") (pinfunction "2_2") (pintype "passive"))
      (node (ref "C194") (pin "2") (pinfunction "2_2") (pintype "passive"))
      (node (ref "C195") (pin "2") (pinfunction "2_2") (pintype "passive"))
      (node (ref "C196") (pin "2") (pinfunction "2_2") (pintype "passive"))
      (node (ref "C197") (pin "2") (pinfunction "2_2") (pintype "passive"))
      (node (ref "C198") (pin "2") (pinfunction "2_2") (pintype "passive"))
      (node (ref "C199") (pin "2") (pinfunction "2_2") (pintype "passive"))
      (node (ref "C200") (pin "2") (pinfunction "2_2") (pintype "passive"))
      (node (ref "C201") (pin "2") (pinfunction "2_2") (pintype "passive"))
      (node (ref "C202") (pin "2") (pinfunction "2_2") (pintype "passive"))
      (node (ref "C203") (pin "2") (pinfunction "2_2") (pintype "passive"))
      (node (ref "C204") (pin "2") (pinfunction "2_2") (pintype "passive"))
      (node (ref "C205") (pin "2") (pinfunction "2_2") (pintype "passive"))
      (node (ref "C206") (pin "2") (pinfunction "2_2") (pintype "passive"))
      (node (ref "C208") (pin "2") (pinfunction "2_2") (pintype "passive"))
      (node (ref "C209") (pin "2") (pinfunction "2_2") (pintype "passive"))
      (node (ref "C210") (pin "2") (pinfunction "2_2") (pintype "passive"))
      (node (ref "C211") (pin "2") (pinfunction "2_2") (pintype "passive"))
      (node (ref "C212") (pin "2") (pinfunction "2_2") (pintype "passive"))
      (node (ref "C213") (pin "2") (pinfunction "2_2") (pintype "passive"))
      (node (ref "C214") (pin "2") (pinfunction "2_2") (pintype "passive"))
      (node (ref "C215") (pin "2") (pinfunction "2_2") (pintype "passive"))
      (node (ref "C472") (pin "2") (pinfunction "2_2") (pintype "passive"))
      (node (ref "C473") (pin "2") (pinfunction "2_2") (pintype "passive"))
      (node (ref "J5") (pin "25") (pinfunction "EH_25") (pintype "passive"))
      (node (ref "J5") (pin "26") (pinfunction "EH_26") (pintype "passive"))
      (node (ref "J5") (pin "27") (pinfunction "EH_27") (pintype "passive"))
      (node (ref "J5") (pin "28") (pinfunction "EH_28") (pintype "passive"))
      (node (ref "J5") (pin "A1") (pinfunction "GND_A1") (pintype "passive"))
      (node (ref "J5") (pin "A12") (pinfunction "GND_A12") (pintype "passive"))
      (node (ref "J5") (pin "B1") (pinfunction "GND_B1") (pintype "passive"))
      (node (ref "J5") (pin "B12") (pinfunction "GND_B12") (pintype "passive"))
      (node (ref "R375") (pin "2") (pinfunction "2_2") (pintype "passive"))
      (node (ref "R383") (pin "2") (pinfunction "2_2") (pintype "passive"))
      (node (ref "R619") (pin "1") (pinfunction "1_1") (pintype "passive"))
      (node (ref "R621") (pin "1") (pinfunction "1_1") (pintype "passive"))
      (node (ref "R622") (pin "1") (pinfunction "1_1") (pintype "passive"))
      (node (ref "R624") (pin "1") (pinfunction "1_1") (pintype "passive"))
      (node (ref "U10") (pin "4") (pinfunction "GND_4") (pintype "power_in"))
      (node (ref "U22") (pin "19") (pinfunction "GND_19") (pintype "passive"))
      (node (ref "U22") (pin "29") (pinfunction "PAD_29") (pintype "passive"))
      (node (ref "U9") (pin "18") (pinfunction "AVSS33_BUCK_18") (pintype "passive"))
      (node (ref "U9") (pin "41") (pinfunction "E-PAD_41") (pintype "passive"))
      (node (ref "Y1") (pin "2") (pinfunction "2_2") (pintype "passive"))
      (node (ref "Y1") (pin "4") (pinfunction "4_4") (pintype "passive"))
    )
    (net (code "62") (name "Net-(C209-Pad1)") (class "Default")
      (node (ref "C209") (pin "1") (pinfunction "1_1") (pintype "passive"))
      (node (ref "R389") (pin "1") (pinfunction "1_1") (pintype "passive"))
      (node (ref "Y1") (pin "3") (pinfunction "3_3") (pintype "passive"))
    )
    (net (code "63") (name "Net-(D1-ANODE)") (class "Default")
      (node (ref "D1") (pin "1") (pinfunction "ANODE_1") (pintype "passive"))
      (node (ref "R381") (pin "2") (pinfunction "2_2") (pintype "passive"))
    )
    (net (code "64") (name "Net-(LED34-ANODE)") (class "Default")
      (node (ref "LED34") (pin "1") (pinfunction "ANODE_1") (pintype "passive"))
      (node (ref "R360") (pin "1") (pinfunction "1_1") (pintype "passive"))
    )
    (net (code "65") (name "Net-(LED35-ANODE)") (class "Default")
      (node (ref "LED35") (pin "1") (pinfunction "ANODE_1") (pintype "passive"))
      (node (ref "R361") (pin "1") (pinfunction "1_1") (pintype "passive"))
    )
    (net (code "66") (name "Net-(U9-LX)") (class "Default")
      (node (ref "L9") (pin "1") (pinfunction "1_1") (pintype "passive"))
      (node (ref "U9") (pin "16") (pinfunction "LX_16") (pintype "passive"))
    )
    (net (code "67") (name "Net-(U9-RSET)") (class "Default")
      (node (ref "R375") (pin "1") (pinfunction "1_1") (pintype "passive"))
      (node (ref "U9") (pin "29") (pinfunction "RSET_29") (pintype "passive"))
    )
    (net (code "68") (name "Net-(U9-VBUS)") (class "Default")
      (node (ref "R366") (pin "2") (pinfunction "2_2") (pintype "passive"))
      (node (ref "U9") (pin "11") (pinfunction "VBUS_11") (pintype "passive"))
    )
    (net (code "69") (name "Net-(U10-NC{slash}SIO3)") (class "Default")
      (node (ref "R385") (pin "1") (pinfunction "1_1") (pintype "passive"))
      (node (ref "U10") (pin "7") (pinfunction "NC/SIO3_7") (pintype "bidirectional"))
    )
    (net (code "70") (name "Net-(U10-SO{slash}SIO1)") (class "Default")
      (node (ref "R384") (pin "2") (pinfunction "2_2") (pintype "passive"))
      (node (ref "U10") (pin "2") (pinfunction "SO/SIO1_2") (pintype "bidirectional"))
    )
    (net (code "71") (name "Net-(U10-WP#{slash}SIO2)") (class "Default")
      (node (ref "R386") (pin "2") (pinfunction "2_2") (pintype "passive"))
      (node (ref "U10") (pin "3") (pinfunction "WP#/SIO2_3") (pintype "bidirectional"))
    )
    (net (code "72") (name "Net-(U22-CC1)") (class "Default")
      (node (ref "R620") (pin "2") (pinfunction "2_2") (pintype "passive"))
      (node (ref "R621") (pin "2") (pinfunction "2_2") (pintype "passive"))
      (node (ref "U22") (pin "1") (pinfunction "CC1_1") (pintype "passive"))
    )
    (net (code "73") (name "Net-(U22-CC2)") (class "Default")
      (node (ref "R622") (pin "2") (pinfunction "2_2") (pintype "passive"))
      (node (ref "R623") (pin "1") (pinfunction "1_1") (pintype "passive"))
      (node (ref "U22") (pin "28") (pinfunction "CC2_28") (pintype "passive"))
    )
    (net (code "74") (name "Net-(U22-CE)") (class "Default")
      (node (ref "R625") (pin "1") (pinfunction "1_1") (pintype "passive"))
      (node (ref "U22") (pin "25") (pinfunction "CE_25") (pintype "passive"))
    )
    (net (code "75") (name "Net-(U22-CURRENT_SETTING_IN_0)") (class "Default")
      (node (ref "R626") (pin "1") (pinfunction "1_1") (pintype "passive"))
      (node (ref "U22") (pin "24") (pinfunction "CURRENT_SETTING_IN_0_24") (pintype "passive"))
    )
    (net (code "76") (name "Net-(U22-CURRENT_SETTING_IN_1)") (class "Default")
      (node (ref "R627") (pin "1") (pinfunction "1_1") (pintype "passive"))
      (node (ref "U22") (pin "23") (pinfunction "CURRENT_SETTING_IN_1_23") (pintype "passive"))
    )
    (net (code "77") (name "Net-(U22-HIGH_Z_CC)") (class "Default")
      (node (ref "R624") (pin "2") (pinfunction "2_2") (pintype "passive"))
      (node (ref "U22") (pin "13") (pinfunction "HIGH_Z_CC_13") (pintype "passive"))
    )
    (net (code "78") (name "Net-(U22-REXT)") (class "Default")
      (node (ref "R619") (pin "2") (pinfunction "2_2") (pintype "passive"))
      (node (ref "U22") (pin "10") (pinfunction "REXT_10") (pintype "passive"))
    )
    (net (code "79") (name "VCC_3V3") (class "Default")
      (node (ref "L7") (pin "1") (pinfunction "1_1") (pintype "passive"))
    )
    (net (code "80") (name "VCC_5V0") (class "Default")
      (node (ref "FB38") (pin "1") (pinfunction "1_1") (pintype "passive"))
    )
    (net (code "81") (name "VCC_5V0_VL160") (class "Default")
      (node (ref "C472") (pin "1") (pinfunction "1_1") (pintype "passive"))
      (node (ref "C473") (pin "1") (pinfunction "1_1") (pintype "passive"))
      (node (ref "FB38") (pin "2") (pinfunction "2_2") (pintype "passive"))
      (node (ref "R625") (pin "2") (pinfunction "2_2") (pintype "passive"))
      (node (ref "R626") (pin "2") (pinfunction "2_2") (pintype "passive"))
      (node (ref "R627") (pin "2") (pinfunction "2_2") (pintype "passive"))
      (node (ref "U22") (pin "26") (pinfunction "VCC5V_26") (pintype "passive"))
      (node (ref "U22") (pin "27") (pinfunction "VCONN_5V_IN_27") (pintype "passive"))
    )
    (net (code "82") (name "unconnected-(J5-SBU1-PadA8)") (class "Default")
      (node (ref "J5") (pin "A8") (pinfunction "SBU1_A8") (pintype "passive"))
    )
    (net (code "83") (name "unconnected-(J5-SBU2-PadB8)") (class "Default")
      (node (ref "J5") (pin "B8") (pinfunction "SBU2_B8") (pintype "passive"))
    )
    (net (code "84") (name "unconnected-(J5-VBUS-PadA4)") (class "Default")
      (node (ref "J5") (pin "A4") (pinfunction "VBUS_A4") (pintype "passive"))
    )
    (net (code "85") (name "unconnected-(J5-VBUS-PadA9)") (class "Default")
      (node (ref "J5") (pin "A9") (pinfunction "VBUS_A9") (pintype "passive"))
    )
    (net (code "86") (name "unconnected-(J5-VBUS-PadB4)") (class "Default")
      (node (ref "J5") (pin "B4") (pinfunction "VBUS_B4") (pintype "passive"))
    )
    (net (code "87") (name "unconnected-(J5-VBUS-PadB9)") (class "Default")
      (node (ref "J5") (pin "B9") (pinfunction "VBUS_B9") (pintype "passive"))
    )
    (net (code "88") (name "unconnected-(U22-ATTACHED_STATUS-Pad16)") (class "Default")
      (node (ref "U22") (pin "16") (pinfunction "ATTACHED_STATUS_16") (pintype "passive"))
    )
    (net (code "89") (name "unconnected-(U22-CURRENT_SETTING_OUT_0-Pad14)") (class "Default")
      (node (ref "U22") (pin "14") (pinfunction "CURRENT_SETTING_OUT_0_14") (pintype "passive"))
    )
    (net (code "90") (name "unconnected-(U22-CURRENT_SETTING_OUT_1-Pad15)") (class "Default")
      (node (ref "U22") (pin "15") (pinfunction "CURRENT_SETTING_OUT_1_15") (pintype "passive"))
    )
    (net (code "91") (name "unconnected-(U22-ORI_STATUS-Pad22)") (class "Default")
      (node (ref "U22") (pin "22") (pinfunction "ORI_STATUS_22") (pintype "passive"))
    )
    (net (code "92") (name "unconnected-(U22-VCONN_OC-Pad11)") (class "Default")
      (node (ref "U22") (pin "11") (pinfunction "VCONN_OC_11") (pintype "passive"))
    )
    (net (code "93") (name "unconnected-(U22-VCONN_UVLO-Pad12)") (class "Default")
      (node (ref "U22") (pin "12") (pinfunction "VCONN_UVLO_12") (pintype "passive"))
    )
  )
)
